# picoPSU-ATX_V2.net
KiCad netlist of a schematic drawn in EAGLE
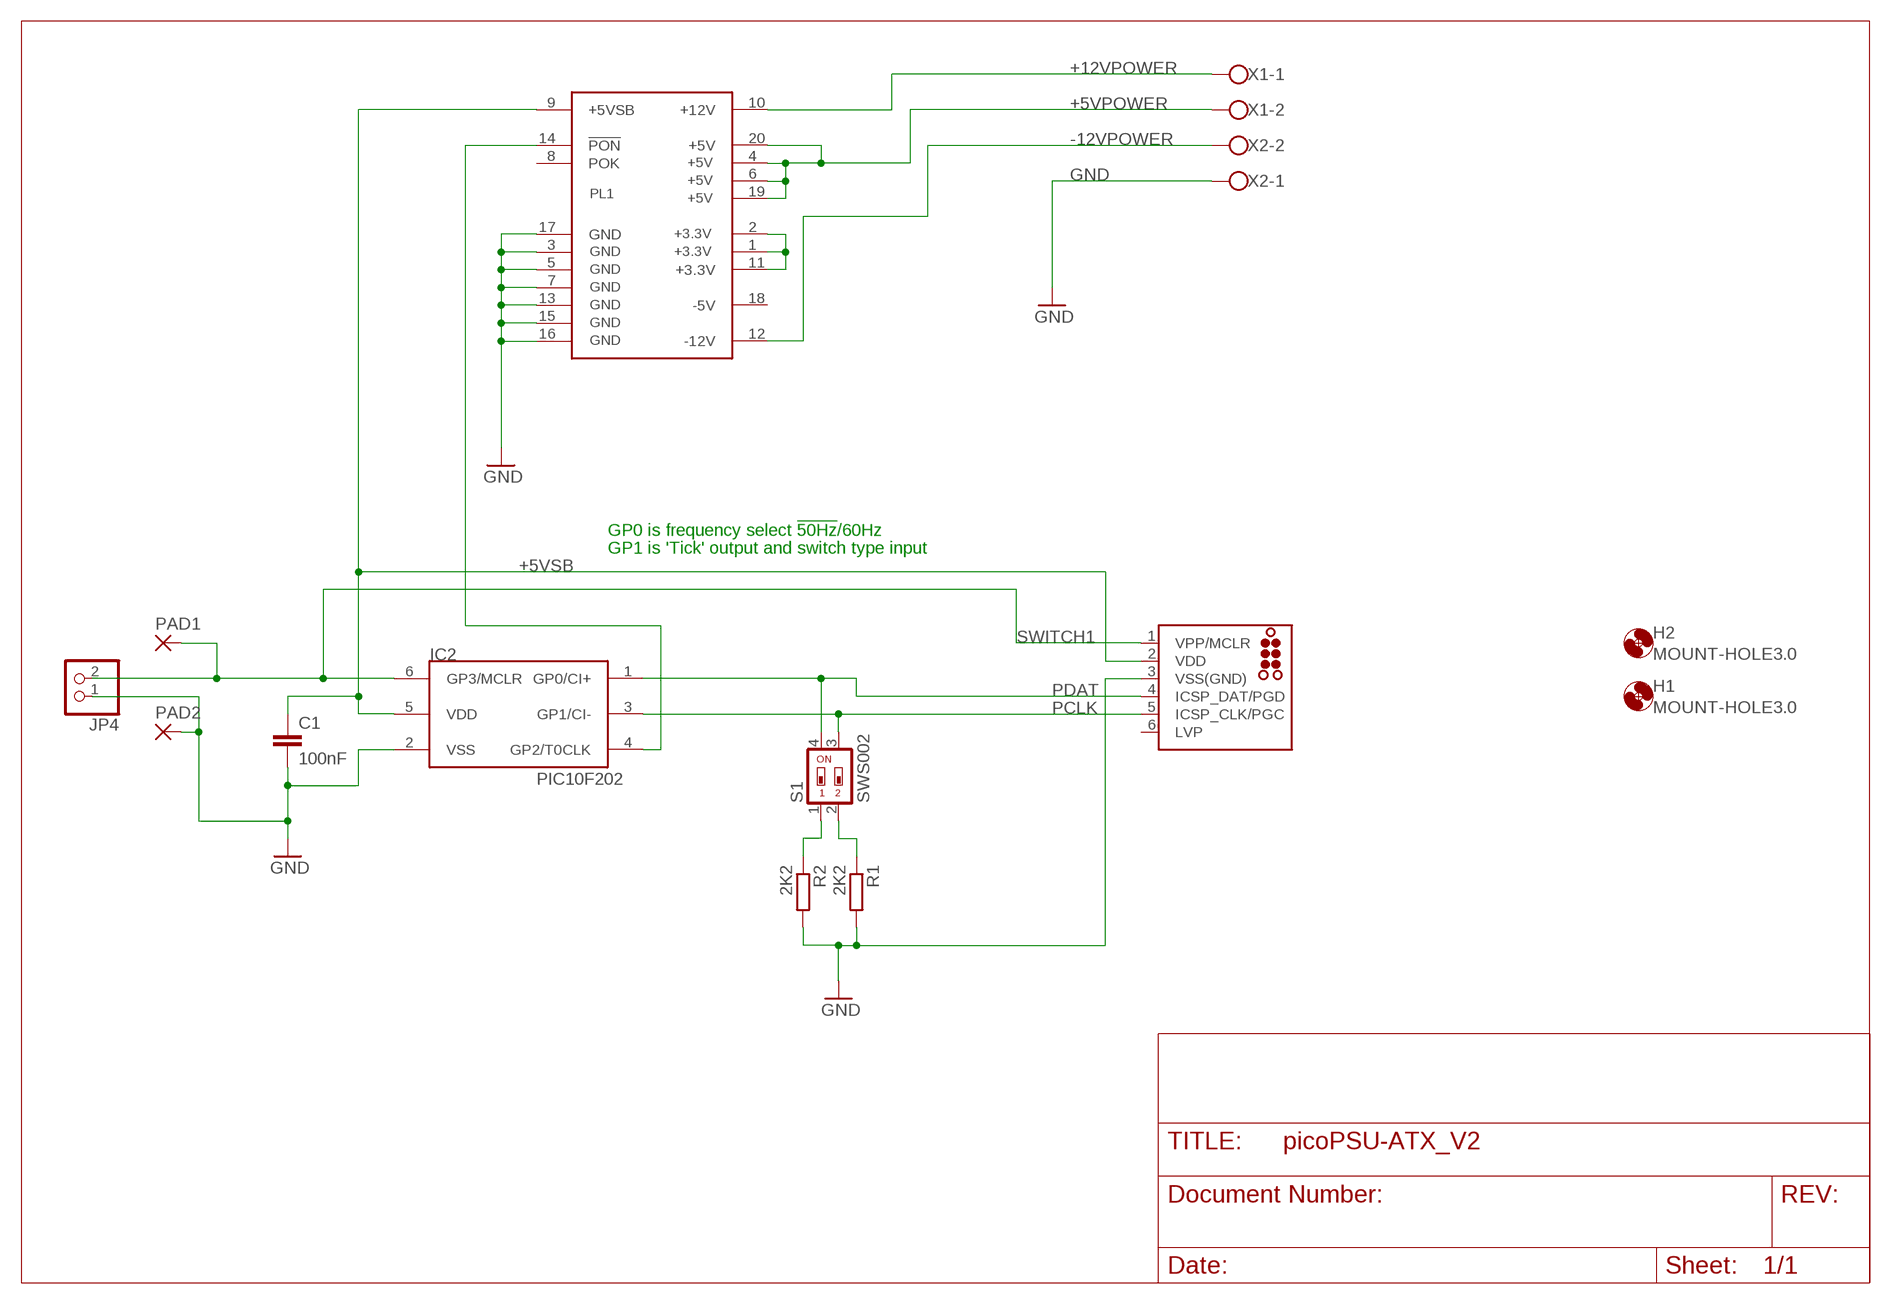
[diagram p0: schematic, sheet 1]

(export (version "E")
  (design (tool "Eeschema 10.0.6"))
  (components
    (comp (ref "C1")
      (value "100nF")
      (footprint "eagle-import:C0805")
      (libsource (lib "eagle-import") (part "C-EUC0805"))
    )
    (comp (ref "H1")
      (value "MOUNT-HOLE3.0")
      (footprint "eagle-import:3,0")
      (libsource (lib "eagle-import") (part "MOUNT-HOLE3.0"))
    )
    (comp (ref "H2")
      (value "MOUNT-HOLE3.0")
      (footprint "eagle-import:3,0")
      (libsource (lib "eagle-import") (part "MOUNT-HOLE3.0"))
    )
    (comp (ref "IC2")
      (value "PIC10F202")
      (footprint "eagle-import:SOT23-6")
      (libsource (lib "eagle-import") (part "PIC10F2OT04"))
    )
    (comp (ref "J1")
      (value "TC2030-MCP-NL")
      (footprint "eagle-import:TC2030-MCP-NL")
      (libsource (lib "eagle-import") (part "TC2030-MCP-NL"))
    )
    (comp (ref "JP4")
      (value "PINHD-1X2")
      (footprint "eagle-import:1X02")
      (libsource (lib "eagle-import") (part "PINHD-1X2"))
    )
    (comp (ref "PAD1")
      (value "2,54/1,1")
      (footprint "eagle-import:2,54_1,1")
      (libsource (lib "eagle-import") (part "2,54/1,1"))
    )
    (comp (ref "PAD2")
      (value "2,54/1,1")
      (footprint "eagle-import:2,54_1,1")
      (libsource (lib "eagle-import") (part "2,54/1,1"))
    )
    (comp (ref "PL1")
      (value "MOLEX39-30-1200")
      (footprint "eagle-import:ATX_RIGHT")
      (libsource (lib "eagle-import") (part "MOLEX39-30-1200"))
    )
    (comp (ref "R1")
      (value "2K2")
      (footprint "eagle-import:R0603")
      (libsource (lib "eagle-import") (part "R-EU_R0603"))
    )
    (comp (ref "R2")
      (value "2K2")
      (footprint "eagle-import:R0603")
      (libsource (lib "eagle-import") (part "R-EU_R0603"))
    )
    (comp (ref "S1")
      (value "SWS002")
      (footprint "eagle-import:SMS-002")
      (libsource (lib "eagle-import") (part "SWS002"))
    )
    (comp (ref "X1")
      (value "W237-102")
      (footprint "eagle-import:W237-102")
      (fields (field (name "MPN") "237-102"))
      (libsource (lib "eagle-import") (part "W237-102"))
    )
    (comp (ref "X2")
      (value "W237-102")
      (footprint "eagle-import:W237-102")
      (fields (field (name "MPN") "237-102"))
      (libsource (lib "eagle-import") (part "W237-102"))
    )
  )
  (nets
    (net (code "1") (name "/+5VPOWER") (class "Default")
      (node (ref "PL1") (pin "19") (pinfunction "+5V_19") (pintype "passive"))
      (node (ref "PL1") (pin "20") (pinfunction "+5V_20") (pintype "passive"))
      (node (ref "PL1") (pin "4") (pinfunction "+5V_4") (pintype "passive"))
      (node (ref "PL1") (pin "6") (pinfunction "+5V_6") (pintype "passive"))
      (node (ref "X1") (pin "2") (pinfunction "KL_2") (pintype "passive"))
    )
    (net (code "2") (name "/+5VSB") (class "Default")
      (node (ref "C1") (pin "1") (pinfunction "1_1") (pintype "passive"))
      (node (ref "IC2") (pin "5") (pinfunction "VDD_5") (pintype "power_in"))
      (node (ref "J1") (pin "2") (pinfunction "VDD_2") (pintype "power_in"))
      (node (ref "PL1") (pin "9") (pinfunction "+5VSB_9") (pintype "passive"))
    )
    (net (code "3") (name "/+12VPOWER") (class "Default")
      (node (ref "PL1") (pin "10") (pinfunction "+12V_10") (pintype "passive"))
      (node (ref "X1") (pin "1") (pinfunction "KL_1") (pintype "passive"))
    )
    (net (code "4") (name "/-12VPOWER") (class "Default")
      (node (ref "PL1") (pin "12") (pinfunction "-12V_12") (pintype "passive"))
      (node (ref "X2") (pin "2") (pinfunction "KL_2") (pintype "passive"))
    )
    (net (code "5") (name "/PCLK") (class "Default")
      (node (ref "IC2") (pin "3") (pinfunction "GP1/CI-_3") (pintype "bidirectional"))
      (node (ref "J1") (pin "5") (pinfunction "ICSP_CLK/PGC_5") (pintype "output"))
      (node (ref "S1") (pin "3") (pinfunction "3_3") (pintype "passive"))
    )
    (net (code "6") (name "/PDAT") (class "Default")
      (node (ref "IC2") (pin "1") (pinfunction "GP0/CI+_1") (pintype "bidirectional"))
      (node (ref "J1") (pin "4") (pinfunction "ICSP_DAT/PGD_4") (pintype "bidirectional"))
      (node (ref "S1") (pin "4") (pinfunction "4_4") (pintype "passive"))
    )
    (net (code "7") (name "/SWITCH1") (class "Default")
      (node (ref "IC2") (pin "6") (pinfunction "GP3/MCLR_6") (pintype "input"))
      (node (ref "J1") (pin "1") (pinfunction "VPP/MCLR_1") (pintype "passive"))
      (node (ref "JP4") (pin "2") (pinfunction "2_2") (pintype "passive"))
      (node (ref "PAD1") (pin "1") (pinfunction "P_1") (pintype "passive"))
    )
    (net (code "8") (name "GND") (class "Default")
      (node (ref "C1") (pin "2") (pinfunction "2_2") (pintype "passive"))
      (node (ref "IC2") (pin "2") (pinfunction "VSS_2") (pintype "power_in"))
      (node (ref "J1") (pin "3") (pinfunction "VSS(GND)_3") (pintype "power_in"))
      (node (ref "JP4") (pin "1") (pinfunction "1_1") (pintype "passive"))
      (node (ref "PAD2") (pin "1") (pinfunction "P_1") (pintype "passive"))
      (node (ref "PL1") (pin "13") (pinfunction "GND_13") (pintype "passive"))
      (node (ref "PL1") (pin "15") (pinfunction "GND_15") (pintype "passive"))
      (node (ref "PL1") (pin "16") (pinfunction "GND_16") (pintype "passive"))
      (node (ref "PL1") (pin "17") (pinfunction "GND_17") (pintype "passive"))
      (node (ref "PL1") (pin "3") (pinfunction "GND_3") (pintype "passive"))
      (node (ref "PL1") (pin "5") (pinfunction "GND_5") (pintype "passive"))
      (node (ref "PL1") (pin "7") (pinfunction "GND_7") (pintype "passive"))
      (node (ref "R1") (pin "2") (pinfunction "2_2") (pintype "passive"))
      (node (ref "R2") (pin "2") (pinfunction "2_2") (pintype "passive"))
      (node (ref "X2") (pin "1") (pinfunction "KL_1") (pintype "passive"))
    )
    (net (code "9") (name "Net-(IC2-GP2{slash}T0CLK)") (class "Default")
      (node (ref "IC2") (pin "4") (pinfunction "GP2/T0CLK_4") (pintype "bidirectional"))
      (node (ref "PL1") (pin "14") (pinfunction "~{PON}_14") (pintype "passive"))
    )
    (net (code "10") (name "Net-(PL1-+3.3V-Pad1)") (class "Default")
      (node (ref "PL1") (pin "1") (pinfunction "+3.3V_1") (pintype "passive"))
      (node (ref "PL1") (pin "11") (pinfunction "+3.3V_11") (pintype "passive"))
      (node (ref "PL1") (pin "2") (pinfunction "+3.3V_2") (pintype "passive"))
    )
    (net (code "11") (name "Net-(R1-Pad1)") (class "Default")
      (node (ref "R1") (pin "1") (pinfunction "1_1") (pintype "passive"))
      (node (ref "S1") (pin "2") (pinfunction "2_2") (pintype "passive"))
    )
    (net (code "12") (name "Net-(R2-Pad1)") (class "Default")
      (node (ref "R2") (pin "1") (pinfunction "1_1") (pintype "passive"))
      (node (ref "S1") (pin "1") (pinfunction "1_1") (pintype "passive"))
    )
    (net (code "13") (name "unconnected-(J1-LVP-Pad6)") (class "Default")
      (node (ref "J1") (pin "6") (pinfunction "LVP_6") (pintype "bidirectional"))
    )
    (net (code "14") (name "unconnected-(PL1--5V-Pad18)") (class "Default")
      (node (ref "PL1") (pin "18") (pinfunction "-5V_18") (pintype "passive"))
    )
    (net (code "15") (name "unconnected-(PL1-POK-Pad8)") (class "Default")
      (node (ref "PL1") (pin "8") (pinfunction "POK_8") (pintype "passive"))
    )
  )
)
